# PowerICs.net
KiCad netlist of a schematic drawn in Altium Designer
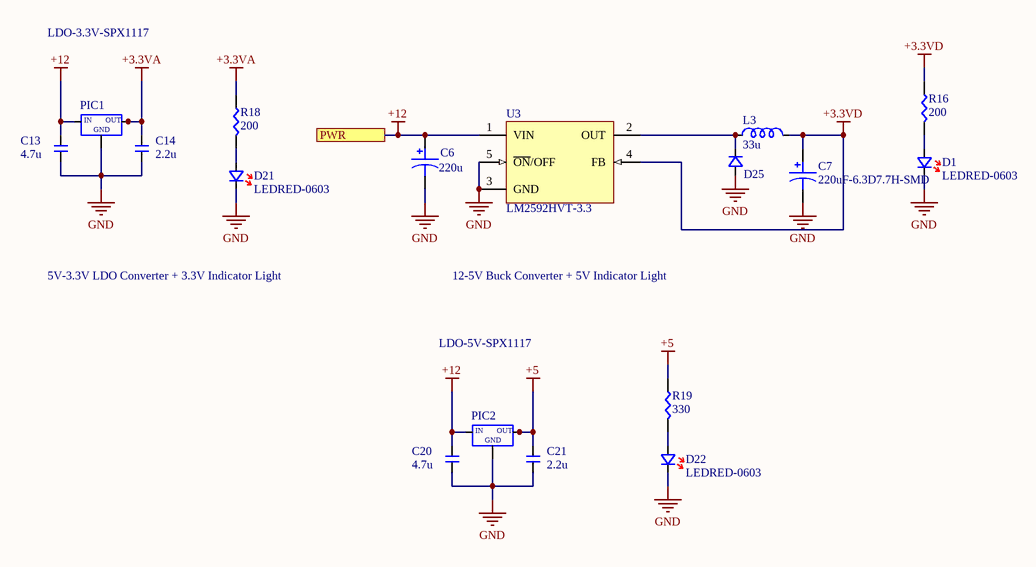
[diagram p0: PowerICs.SchDoc]

(export (version "E")
  (design (tool "Eeschema 10.0.6"))
  (components
    (comp (ref "C6")
      (value "220u")
      (footprint "CAP-6.3D7.7H-SMD")
      (description "220uF-6.3D7.7H-SMD\r\n25v, 600ma Ripple")
      (libsource (lib "ife19_Elec_Library") (part "CAP-6.3D7.7H-SMD"))
    )
    (comp (ref "C7")
      (value "220uF-6.3D7.7H-SMD")
      (footprint "CAP-6.3D7.7H-SMD")
      (libsource (lib "ife19_Elec_Library") (part "CAP-6.3D7.7H-SMD"))
    )
    (comp (ref "C13")
      (value "4.7u")
      (footprint "CAP-0603")
      (libsource (lib "ife19_Elec_Library") (part "CAP-0603"))
    )
    (comp (ref "C14")
      (value "2.2u")
      (footprint "CAP-0603")
      (libsource (lib "ife19_Elec_Library") (part "CAP-0603"))
    )
    (comp (ref "C20")
      (value "4.7u")
      (footprint "CAP-0603")
      (libsource (lib "ife19_Elec_Library") (part "CAP-0603"))
    )
    (comp (ref "C21")
      (value "2.2u")
      (footprint "CAP-0603")
      (libsource (lib "ife19_Elec_Library") (part "CAP-0603"))
    )
    (comp (ref "D1")
      (value "LEDRED-0603")
      (footprint "LEDRED-0603")
      (libsource (lib "ife19_Elec_Library") (part "LEDRED-0603"))
    )
    (comp (ref "D21")
      (value "LEDRED-0603")
      (footprint "LEDRED-0603")
      (libsource (lib "ife19_Elec_Library") (part "LEDRED-0603"))
    )
    (comp (ref "D22")
      (value "LEDRED-0603")
      (footprint "LEDRED-0603")
      (libsource (lib "ife19_Elec_Library") (part "LEDRED-0603"))
    )
    (comp (ref "D25")
      (value "~")
      (footprint "SOD123")
      (libsource (lib "ife19_Elec_Library") (part "DIODE-SOD123"))
    )
    (comp (ref "L3")
      (value "33u")
      (footprint "IND-6045")
      (libsource (lib "ife19_Elec_Library") (part "IND-6045"))
    )
    (comp (ref "PIC1")
      (value "LDO-3.3V-SPX1117")
      (footprint "SOT223")
      (libsource (lib "ife19_Elec_Library") (part "LDO-SOT223_SPX1117"))
    )
    (comp (ref "PIC2")
      (value "LDO-5V-SPX1117")
      (footprint "SOT223")
      (libsource (lib "ife19_Elec_Library") (part "LDO-SOT223_SPX1117"))
    )
    (comp (ref "R16")
      (value "200")
      (footprint "RES-0603")
      (libsource (lib "ife19_Elec_Library") (part "RES-0603"))
    )
    (comp (ref "R18")
      (value "200")
      (footprint "RES-0603")
      (libsource (lib "ife19_Elec_Library") (part "RES-0603"))
    )
    (comp (ref "R19")
      (value "330")
      (footprint "RES-0603")
      (libsource (lib "ife19_Elec_Library") (part "RES-0603"))
    )
    (comp (ref "U3")
      (value "LM2592HVT-3.3")
      (footprint "T05D")
      (description "SIMPLE SWITCHER® Power Converter 150 KHz 2A Step-Down Voltage Regulator, 5-pin TO-220")
      (fields (field (name "MANUFACTURER") "National Semiconductor"))
      (libsource (lib "Altium Content Vault") (part "PM-REG-LM2575HVT-12"))
    )
  )
  (nets
    (net (code "1") (name "+3.3VA") (class "Default")
      (node (ref "C14") (pin "2") (pinfunction "2_2") (pintype "passive"))
      (node (ref "PIC1") (pin "2") (pinfunction "2_2") (pintype "passive"))
      (node (ref "PIC1") (pin "4") (pinfunction "4_4") (pintype "passive"))
      (node (ref "R18") (pin "1") (pinfunction "1_1") (pintype "passive"))
    )
    (net (code "2") (name "+3.3VD") (class "Default")
      (node (ref "C7") (pin "POS") (pinfunction "+_POS") (pintype "passive"))
      (node (ref "L3") (pin "2") (pinfunction "2_2") (pintype "passive"))
      (node (ref "R16") (pin "1") (pinfunction "1_1") (pintype "passive"))
      (node (ref "U3") (pin "4") (pinfunction "FB_4") (pintype "input"))
    )
    (net (code "3") (name "+5") (class "Default")
      (node (ref "C21") (pin "2") (pinfunction "2_2") (pintype "passive"))
      (node (ref "PIC2") (pin "2") (pinfunction "2_2") (pintype "passive"))
      (node (ref "PIC2") (pin "4") (pinfunction "4_4") (pintype "passive"))
      (node (ref "R19") (pin "1") (pinfunction "1_1") (pintype "passive"))
    )
    (net (code "4") (name "+12") (class "Default")
      (node (ref "C13") (pin "2") (pinfunction "2_2") (pintype "passive"))
      (node (ref "C20") (pin "2") (pinfunction "2_2") (pintype "passive"))
      (node (ref "C6") (pin "POS") (pinfunction "+_POS") (pintype "passive"))
      (node (ref "PIC1") (pin "3") (pinfunction "3_3") (pintype "passive"))
      (node (ref "PIC2") (pin "3") (pinfunction "3_3") (pintype "passive"))
      (node (ref "U3") (pin "1") (pinfunction "VIN_1") (pintype "power_in"))
    )
    (net (code "5") (name "GND") (class "Default")
      (node (ref "C13") (pin "1") (pinfunction "1_1") (pintype "passive"))
      (node (ref "C14") (pin "1") (pinfunction "1_1") (pintype "passive"))
      (node (ref "C20") (pin "1") (pinfunction "1_1") (pintype "passive"))
      (node (ref "C21") (pin "1") (pinfunction "1_1") (pintype "passive"))
      (node (ref "C6") (pin "NEG") (pinfunction "-_NEG") (pintype "passive"))
      (node (ref "C7") (pin "NEG") (pinfunction "-_NEG") (pintype "passive"))
      (node (ref "D1") (pin "K") (pinfunction "K_K") (pintype "passive"))
      (node (ref "D21") (pin "K") (pinfunction "K_K") (pintype "passive"))
      (node (ref "D22") (pin "K") (pinfunction "K_K") (pintype "passive"))
      (node (ref "D25") (pin "A") (pinfunction "A_A") (pintype "passive"))
      (node (ref "PIC1") (pin "1") (pinfunction "1_1") (pintype "passive"))
      (node (ref "PIC2") (pin "1") (pinfunction "1_1") (pintype "passive"))
      (node (ref "U3") (pin "3") (pinfunction "GND_3") (pintype "power_in"))
      (node (ref "U3") (pin "5") (pinfunction "~{ON}/OFF_5") (pintype "input"))
    )
    (net (code "6") (name "Net-(D1-PadA)") (class "Default")
      (node (ref "D1") (pin "A") (pinfunction "A_A") (pintype "passive"))
      (node (ref "R16") (pin "2") (pinfunction "2_2") (pintype "passive"))
    )
    (net (code "7") (name "Net-(D21-PadA)") (class "Default")
      (node (ref "D21") (pin "A") (pinfunction "A_A") (pintype "passive"))
      (node (ref "R18") (pin "2") (pinfunction "2_2") (pintype "passive"))
    )
    (net (code "8") (name "Net-(D22-PadA)") (class "Default")
      (node (ref "D22") (pin "A") (pinfunction "A_A") (pintype "passive"))
      (node (ref "R19") (pin "2") (pinfunction "2_2") (pintype "passive"))
    )
    (net (code "9") (name "Net-(U3-OUT)") (class "Default")
      (node (ref "D25") (pin "K") (pinfunction "K_K") (pintype "passive"))
      (node (ref "L3") (pin "1") (pinfunction "1_1") (pintype "passive"))
      (node (ref "U3") (pin "2") (pinfunction "OUT_2") (pintype "power_in"))
    )
  )
)
